# Power.net
KiCad netlist of a schematic drawn in Altium Designer
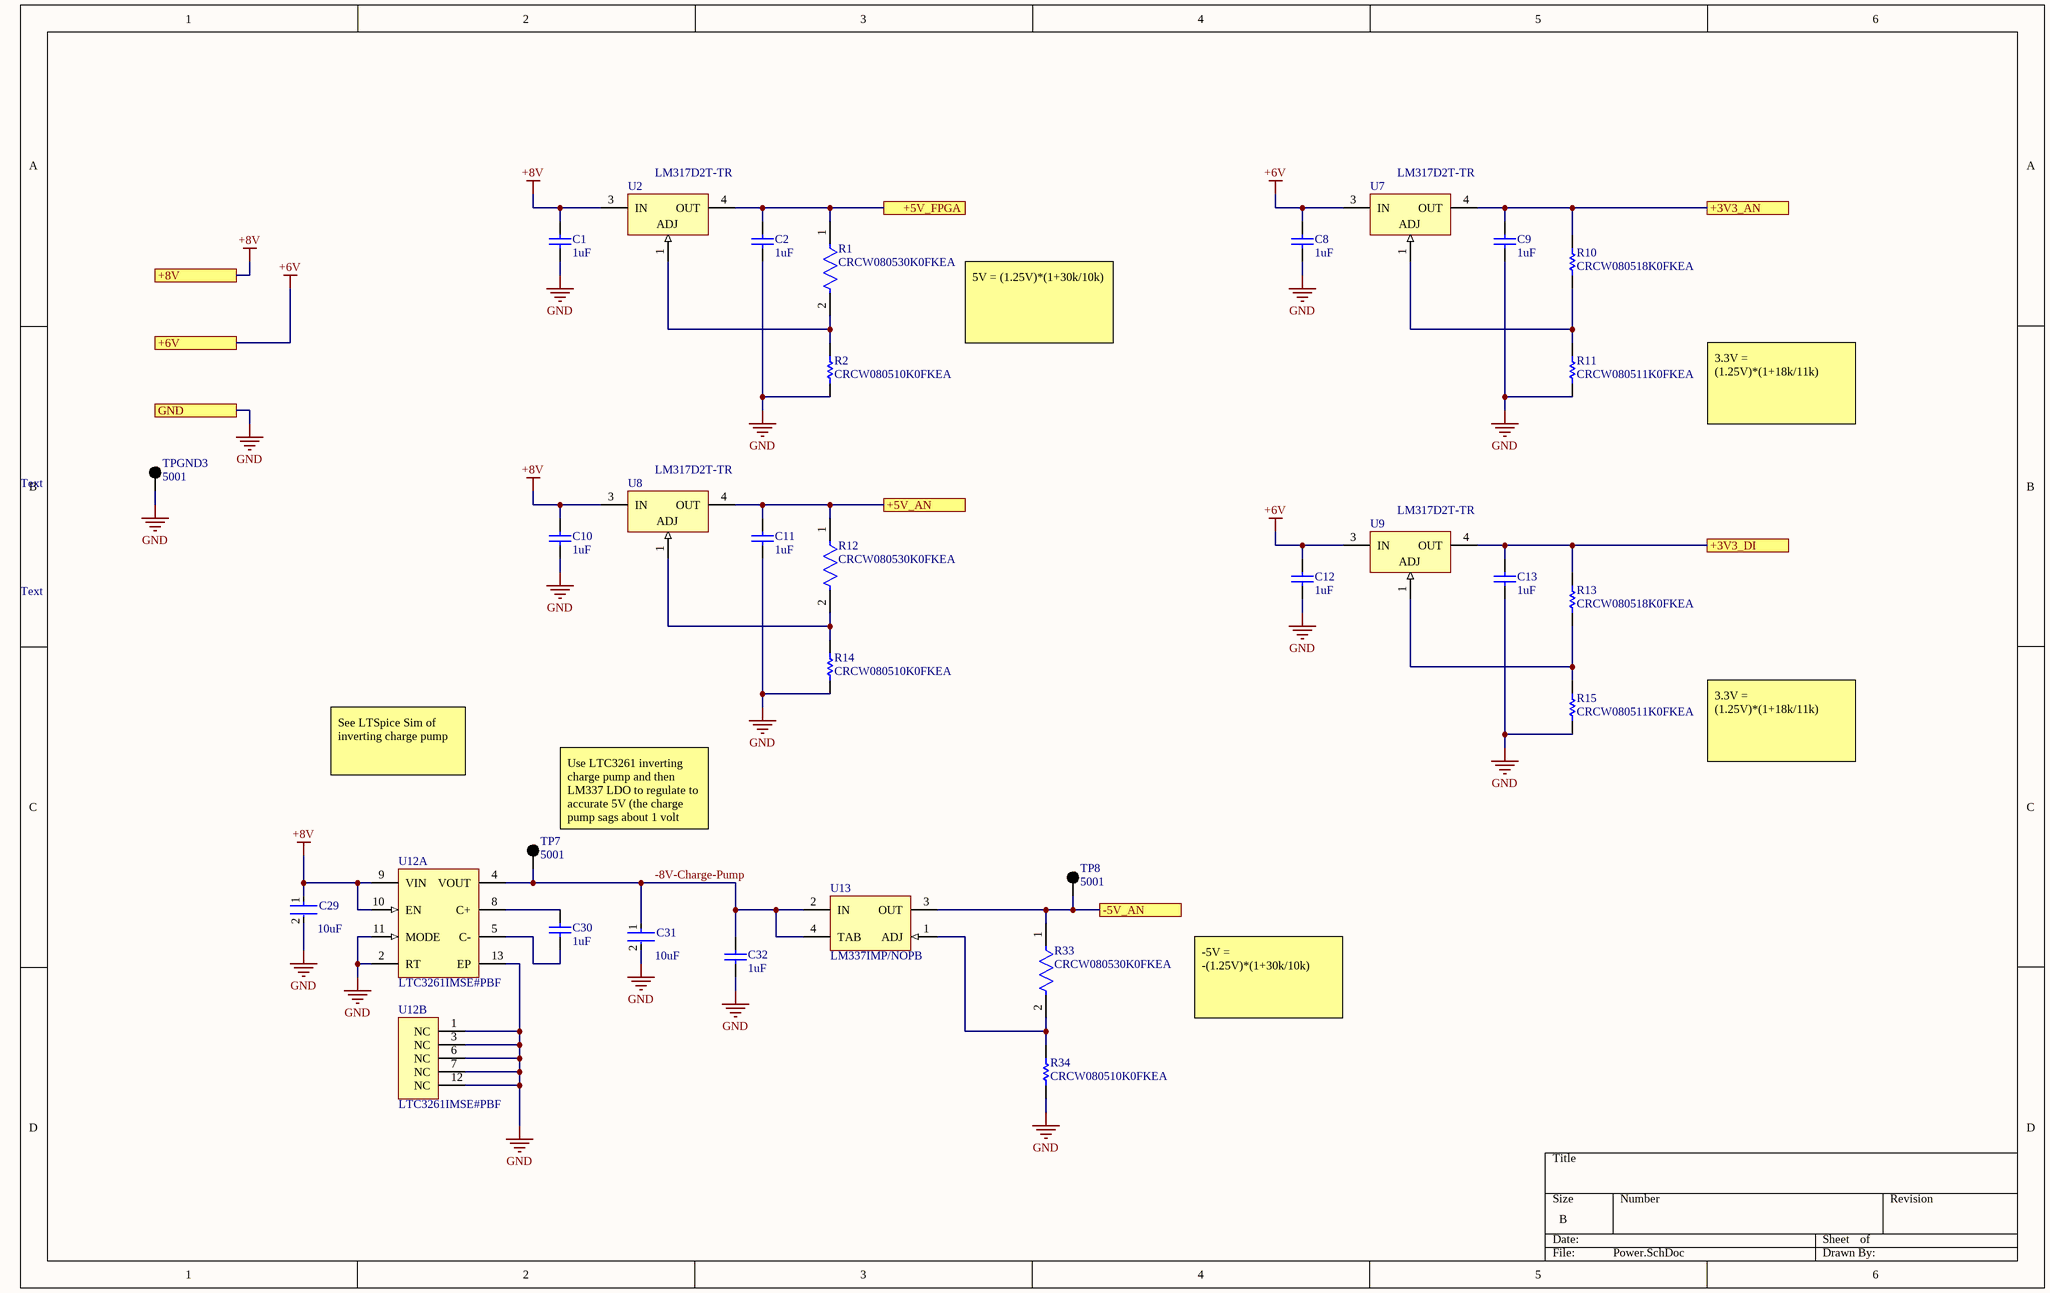
[diagram p0: Power.SchDoc]

(export (version "E")
  (design (tool "Eeschema 10.0.6"))
  (components
    (comp (ref "C1")
      (value "1uF")
      (footprint "CAPC2013X100X50NL20T25")
      (fields (field (name "PART NUMBER") "C0805X105K3RACTU") (field (name "MANUFACTURER") "Kemet"))
      (libsource (lib "Altium Content Vault") (part "CAP"))
    )
    (comp (ref "C2")
      (value "1uF")
      (footprint "CAPC2013X100X50NL20T25")
      (fields (field (name "PART NUMBER") "C0805X105K3RACTU") (field (name "MANUFACTURER") "Kemet"))
      (libsource (lib "Altium Content Vault") (part "CAP"))
    )
    (comp (ref "C8")
      (value "1uF")
      (footprint "CAPC2013X100X50NL20T25")
      (fields (field (name "PART NUMBER") "C0805X105K3RACTU") (field (name "MANUFACTURER") "Kemet"))
      (libsource (lib "Altium Content Vault") (part "CAP"))
    )
    (comp (ref "C9")
      (value "1uF")
      (footprint "CAPC2013X100X50NL20T25")
      (fields (field (name "PART NUMBER") "C0805X105K3RACTU") (field (name "MANUFACTURER") "Kemet"))
      (libsource (lib "Altium Content Vault") (part "CAP"))
    )
    (comp (ref "C10")
      (value "1uF")
      (footprint "CAPC2013X100X50NL20T25")
      (fields (field (name "PART NUMBER") "C0805X105K3RACTU") (field (name "MANUFACTURER") "Kemet"))
      (libsource (lib "Altium Content Vault") (part "CAP"))
    )
    (comp (ref "C11")
      (value "1uF")
      (footprint "CAPC2013X100X50NL20T25")
      (fields (field (name "PART NUMBER") "C0805X105K3RACTU") (field (name "MANUFACTURER") "Kemet"))
      (libsource (lib "Altium Content Vault") (part "CAP"))
    )
    (comp (ref "C12")
      (value "1uF")
      (footprint "CAPC2013X100X50NL20T25")
      (fields (field (name "PART NUMBER") "C0805X105K3RACTU") (field (name "MANUFACTURER") "Kemet"))
      (libsource (lib "Altium Content Vault") (part "CAP"))
    )
    (comp (ref "C13")
      (value "1uF")
      (footprint "CAPC2013X100X50NL20T25")
      (fields (field (name "PART NUMBER") "C0805X105K3RACTU") (field (name "MANUFACTURER") "Kemet"))
      (libsource (lib "Altium Content Vault") (part "CAP"))
    )
    (comp (ref "C29")
      (value "CGA5L1X7R1E106K160AC")
      (footprint "FP-CGA5L-0_3-0_1-MFG")
      (description "Cap Ceramic 10uF 25V X7R 10% Pad SMD 1206 +125°C Automotive T/R")
      (fields (field (name "TOLERANCE") "10%") (field (name "CAPACITANCE") "10uF"))
      (libsource (lib "Altium Content Vault") (part "b4654b650e69147ec39a6b967a45e02"))
    )
    (comp (ref "C30")
      (value "1uF")
      (footprint "CAPC2013X100X50NL20T25")
      (fields (field (name "PART NUMBER") "C0805X105K3RACTU") (field (name "MANUFACTURER") "Kemet"))
      (libsource (lib "Altium Content Vault") (part "CAP"))
    )
    (comp (ref "C31")
      (value "CGA5L1X7R1E106K160AC")
      (footprint "FP-CGA5L-0_3-0_1-MFG")
      (description "Cap Ceramic 10uF 25V X7R 10% Pad SMD 1206 +125°C Automotive T/R")
      (fields (field (name "TOLERANCE") "10%") (field (name "CAPACITANCE") "10uF"))
      (libsource (lib "Altium Content Vault") (part "b4654b650e69147ec39a6b967a45e02"))
    )
    (comp (ref "C32")
      (value "1uF")
      (footprint "CAPC2013X100X50NL20T25")
      (fields (field (name "PART NUMBER") "C0805X105K3RACTU") (field (name "MANUFACTURER") "Kemet"))
      (libsource (lib "Altium Content Vault") (part "CAP"))
    )
    (comp (ref "R1")
      (value "CRCW080530K0FKEA")
      (footprint "FP-CRCW0805-e3-MFG")
      (description "RES Thick Film, 30kΩ, 1%, 0.125W, 100ppm/°C, 0805")
      (fields (field (name "TOLERANCE") "1%"))
      (libsource (lib "Altium Content Vault") (part "1029c3af85768c4190bb7ad29bc67b5"))
    )
    (comp (ref "R2")
      (value "CRCW080510K0FKEA")
      (footprint "RESC2013X50X30NL20T20")
      (fields (field (name "MANUFACTURER") "Vishay Dale"))
      (libsource (lib "Altium Content Vault") (part "RES"))
    )
    (comp (ref "R10")
      (value "CRCW080518K0FKEA")
      (footprint "RESC2013X50X30NL20T20")
      (fields (field (name "MANUFACTURER") "Vishay Dale"))
      (libsource (lib "Altium Content Vault") (part "RES"))
    )
    (comp (ref "R11")
      (value "CRCW080511K0FKEA")
      (footprint "RESC2013X50X30NL20T20")
      (fields (field (name "MANUFACTURER") "Vishay Dale"))
      (libsource (lib "Altium Content Vault") (part "RES"))
    )
    (comp (ref "R12")
      (value "CRCW080530K0FKEA")
      (footprint "FP-CRCW0805-e3-MFG")
      (description "RES Thick Film, 30kΩ, 1%, 0.125W, 100ppm/°C, 0805")
      (fields (field (name "TOLERANCE") "1%"))
      (libsource (lib "Altium Content Vault") (part "1029c3af85768c4190bb7ad29bc67b5"))
    )
    (comp (ref "R13")
      (value "CRCW080518K0FKEA")
      (footprint "RESC2013X50X30NL20T20")
      (fields (field (name "MANUFACTURER") "Vishay Dale"))
      (libsource (lib "Altium Content Vault") (part "RES"))
    )
    (comp (ref "R14")
      (value "CRCW080510K0FKEA")
      (footprint "RESC2013X50X30NL20T20")
      (fields (field (name "MANUFACTURER") "Vishay Dale"))
      (libsource (lib "Altium Content Vault") (part "RES"))
    )
    (comp (ref "R15")
      (value "CRCW080511K0FKEA")
      (footprint "RESC2013X50X30NL20T20")
      (fields (field (name "MANUFACTURER") "Vishay Dale"))
      (libsource (lib "Altium Content Vault") (part "RES"))
    )
    (comp (ref "R33")
      (value "CRCW080530K0FKEA")
      (footprint "FP-CRCW0805-e3-MFG")
      (description "RES Thick Film, 30kΩ, 1%, 0.125W, 100ppm/°C, 0805")
      (fields (field (name "TOLERANCE") "1%"))
      (libsource (lib "Altium Content Vault") (part "1029c3af85768c4190bb7ad29bc67b5"))
    )
    (comp (ref "R34")
      (value "CRCW080510K0FKEA")
      (footprint "RESC2013X50X30NL20T20")
      (fields (field (name "MANUFACTURER") "Vishay Dale"))
      (libsource (lib "Altium Content Vault") (part "RES"))
    )
    (comp (ref "TP7")
      (value "5001")
      (footprint "KSTN-5001")
      (description "Test Point, Black, 1-Pin THD, RoHS, Bulk")
      (fields (field (name "MANUFACTURER") "Keystone"))
      (libsource (lib "Altium Content Vault") (part "KSTN-TP-5001"))
    )
    (comp (ref "TP8")
      (value "5001")
      (footprint "KSTN-5001")
      (description "Test Point, Black, 1-Pin THD, RoHS, Bulk")
      (fields (field (name "MANUFACTURER") "Keystone"))
      (libsource (lib "Altium Content Vault") (part "KSTN-TP-5001"))
    )
    (comp (ref "TPGND3")
      (value "5001")
      (footprint "KSTN-5001")
      (description "Test Point, Black, 1-Pin THD, RoHS, Bulk")
      (fields (field (name "MANUFACTURER") "Keystone"))
      (libsource (lib "Altium Content Vault") (part "KSTN-TP-5001"))
    )
    (comp (ref "U2")
      (value "LM317D2T-TR")
      (footprint "TO-263_N")
      (description "1.5A, 1.2V to 37V Adjustable Voltage Regulator, 3-Pin D2PAK, Tape and Reel")
      (libsource (lib "Altium Content Vault") (part "PM-REG-217-SOT3"))
    )
    (comp (ref "U7")
      (value "LM317D2T-TR")
      (footprint "TO-263_N")
      (description "1.5A, 1.2V to 37V Adjustable Voltage Regulator, 3-Pin D2PAK, Tape and Reel")
      (libsource (lib "Altium Content Vault") (part "PM-REG-217-SOT3"))
    )
    (comp (ref "U8")
      (value "LM317D2T-TR")
      (footprint "TO-263_N")
      (description "1.5A, 1.2V to 37V Adjustable Voltage Regulator, 3-Pin D2PAK, Tape and Reel")
      (libsource (lib "Altium Content Vault") (part "PM-REG-217-SOT3"))
    )
    (comp (ref "U9")
      (value "LM317D2T-TR")
      (footprint "TO-263_N")
      (description "1.5A, 1.2V to 37V Adjustable Voltage Regulator, 3-Pin D2PAK, Tape and Reel")
      (libsource (lib "Altium Content Vault") (part "PM-REG-217-SOT3"))
    )
    (comp (ref "U12")
      (value "LTC3261IMSE#PBF")
      (footprint "LT-MSE-12-EDP_M")
      (fields (field (name "MANUFACTURER") "Linear Technology"))
      (libsource (lib "Altium Content Vault") (part "LT-LTC3261-MSE-12"))
    )
    (comp (ref "U13")
      (value "LM337IMP/NOPB")
      (footprint "DCY0004A_L")
      (description "3-Terminal Adjustable Negative Regulator, 4-pin SOT-223, Pb-Free")
      (fields (field (name "MANUFACTURER") "Texas Instruments"))
      (libsource (lib "Altium Content Vault") (part "PM-REG-LM337ADJ-SOT4"))
    )
  )
  (nets
    (net (code "1") (name "+6V") (class "Default")
      (node (ref "C12") (pin "2") (pinfunction "2_2") (pintype "passive"))
      (node (ref "C8") (pin "2") (pinfunction "2_2") (pintype "passive"))
      (node (ref "U7") (pin "3") (pinfunction "IN_3") (pintype "power_in"))
      (node (ref "U9") (pin "3") (pinfunction "IN_3") (pintype "power_in"))
    )
    (net (code "2") (name "+8V") (class "Default")
      (node (ref "C1") (pin "2") (pinfunction "2_2") (pintype "passive"))
      (node (ref "C10") (pin "2") (pinfunction "2_2") (pintype "passive"))
      (node (ref "C29") (pin "1") (pinfunction "1_1") (pintype "passive"))
      (node (ref "U12") (pin "10") (pinfunction "EN_10") (pintype "input"))
      (node (ref "U12") (pin "9") (pinfunction "VIN_9") (pintype "power_in"))
      (node (ref "U2") (pin "3") (pinfunction "IN_3") (pintype "power_in"))
      (node (ref "U8") (pin "3") (pinfunction "IN_3") (pintype "power_in"))
    )
    (net (code "3") (name "/+3V3_AN") (class "Default")
      (node (ref "C9") (pin "2") (pinfunction "2_2") (pintype "passive"))
      (node (ref "R10") (pin "2") (pinfunction "2_2") (pintype "passive"))
      (node (ref "U7") (pin "4") (pinfunction "OUT_4") (pintype "power_in"))
    )
    (net (code "4") (name "/+3V3_DI") (class "Default")
      (node (ref "C13") (pin "2") (pinfunction "2_2") (pintype "passive"))
      (node (ref "R13") (pin "2") (pinfunction "2_2") (pintype "passive"))
      (node (ref "U9") (pin "4") (pinfunction "OUT_4") (pintype "power_in"))
    )
    (net (code "5") (name "/+5V_AN") (class "Default")
      (node (ref "C11") (pin "2") (pinfunction "2_2") (pintype "passive"))
      (node (ref "R12") (pin "1") (pinfunction "1_1") (pintype "passive"))
      (node (ref "U8") (pin "4") (pinfunction "OUT_4") (pintype "power_in"))
    )
    (net (code "6") (name "/+5V_FPGA") (class "Default")
      (node (ref "C2") (pin "2") (pinfunction "2_2") (pintype "passive"))
      (node (ref "R1") (pin "1") (pinfunction "1_1") (pintype "passive"))
      (node (ref "U2") (pin "4") (pinfunction "OUT_4") (pintype "power_in"))
    )
    (net (code "7") (name "/-5V_AN") (class "Default")
      (node (ref "R33") (pin "1") (pinfunction "1_1") (pintype "passive"))
      (node (ref "TP8") (pin "1") (pintype "passive"))
      (node (ref "U13") (pin "3") (pinfunction "OUT_3") (pintype "power_in"))
    )
    (net (code "8") (name "/-8V-Charge-Pump") (class "Default")
      (node (ref "C31") (pin "1") (pinfunction "1_1") (pintype "passive"))
      (node (ref "C32") (pin "2") (pinfunction "2_2") (pintype "passive"))
      (node (ref "TP7") (pin "1") (pintype "passive"))
      (node (ref "U12") (pin "4") (pinfunction "VOUT_4") (pintype "power_in"))
      (node (ref "U13") (pin "2") (pinfunction "IN_2") (pintype "power_in"))
      (node (ref "U13") (pin "4") (pinfunction "TAB_4") (pintype "power_in"))
    )
    (net (code "9") (name "GND") (class "Default")
      (node (ref "C1") (pin "1") (pinfunction "1_1") (pintype "passive"))
      (node (ref "C10") (pin "1") (pinfunction "1_1") (pintype "passive"))
      (node (ref "C11") (pin "1") (pinfunction "1_1") (pintype "passive"))
      (node (ref "C12") (pin "1") (pinfunction "1_1") (pintype "passive"))
      (node (ref "C13") (pin "1") (pinfunction "1_1") (pintype "passive"))
      (node (ref "C2") (pin "1") (pinfunction "1_1") (pintype "passive"))
      (node (ref "C29") (pin "2") (pinfunction "2_2") (pintype "passive"))
      (node (ref "C31") (pin "2") (pinfunction "2_2") (pintype "passive"))
      (node (ref "C32") (pin "1") (pinfunction "1_1") (pintype "passive"))
      (node (ref "C8") (pin "1") (pinfunction "1_1") (pintype "passive"))
      (node (ref "C9") (pin "1") (pinfunction "1_1") (pintype "passive"))
      (node (ref "R11") (pin "1") (pinfunction "1_1") (pintype "passive"))
      (node (ref "R14") (pin "2") (pinfunction "2_2") (pintype "passive"))
      (node (ref "R15") (pin "1") (pinfunction "1_1") (pintype "passive"))
      (node (ref "R2") (pin "2") (pinfunction "2_2") (pintype "passive"))
      (node (ref "R34") (pin "2") (pinfunction "2_2") (pintype "passive"))
      (node (ref "TPGND3") (pin "1") (pintype "passive"))
      (node (ref "U12") (pin "1") (pinfunction "NC_1") (pintype "passive"))
      (node (ref "U12") (pin "11") (pinfunction "MODE_11") (pintype "input"))
      (node (ref "U12") (pin "12") (pinfunction "NC_12") (pintype "passive"))
      (node (ref "U12") (pin "13") (pinfunction "EP_13") (pintype "power_in"))
      (node (ref "U12") (pin "2") (pinfunction "RT_2") (pintype "passive"))
      (node (ref "U12") (pin "3") (pinfunction "NC_3") (pintype "passive"))
      (node (ref "U12") (pin "6") (pinfunction "NC_6") (pintype "passive"))
      (node (ref "U12") (pin "7") (pinfunction "NC_7") (pintype "passive"))
    )
    (net (code "10") (name "Net-(U2-ADJ)") (class "Default")
      (node (ref "R1") (pin "2") (pinfunction "2_2") (pintype "passive"))
      (node (ref "R2") (pin "1") (pinfunction "1_1") (pintype "passive"))
      (node (ref "U2") (pin "1") (pinfunction "ADJ_1") (pintype "input"))
    )
    (net (code "11") (name "Net-(U7-ADJ)") (class "Default")
      (node (ref "R10") (pin "1") (pinfunction "1_1") (pintype "passive"))
      (node (ref "R11") (pin "2") (pinfunction "2_2") (pintype "passive"))
      (node (ref "U7") (pin "1") (pinfunction "ADJ_1") (pintype "input"))
    )
    (net (code "12") (name "Net-(U8-ADJ)") (class "Default")
      (node (ref "R12") (pin "2") (pinfunction "2_2") (pintype "passive"))
      (node (ref "R14") (pin "1") (pinfunction "1_1") (pintype "passive"))
      (node (ref "U8") (pin "1") (pinfunction "ADJ_1") (pintype "input"))
    )
    (net (code "13") (name "Net-(U9-ADJ)") (class "Default")
      (node (ref "R13") (pin "1") (pinfunction "1_1") (pintype "passive"))
      (node (ref "R15") (pin "2") (pinfunction "2_2") (pintype "passive"))
      (node (ref "U9") (pin "1") (pinfunction "ADJ_1") (pintype "input"))
    )
    (net (code "14") (name "Net-(U12A-C+)") (class "Default")
      (node (ref "C30") (pin "2") (pinfunction "2_2") (pintype "passive"))
      (node (ref "U12") (pin "8") (pinfunction "C+_8") (pintype "passive"))
    )
    (net (code "15") (name "Net-(U12A-C-)") (class "Default")
      (node (ref "C30") (pin "1") (pinfunction "1_1") (pintype "passive"))
      (node (ref "U12") (pin "5") (pinfunction "C-_5") (pintype "passive"))
    )
    (net (code "16") (name "Net-(U13-ADJ)") (class "Default")
      (node (ref "R33") (pin "2") (pinfunction "2_2") (pintype "passive"))
      (node (ref "R34") (pin "1") (pinfunction "1_1") (pintype "passive"))
      (node (ref "U13") (pin "1") (pinfunction "ADJ_1") (pintype "input"))
    )
  )
)
